# Relay.net
KiCad netlist of a schematic drawn in Altium Designer
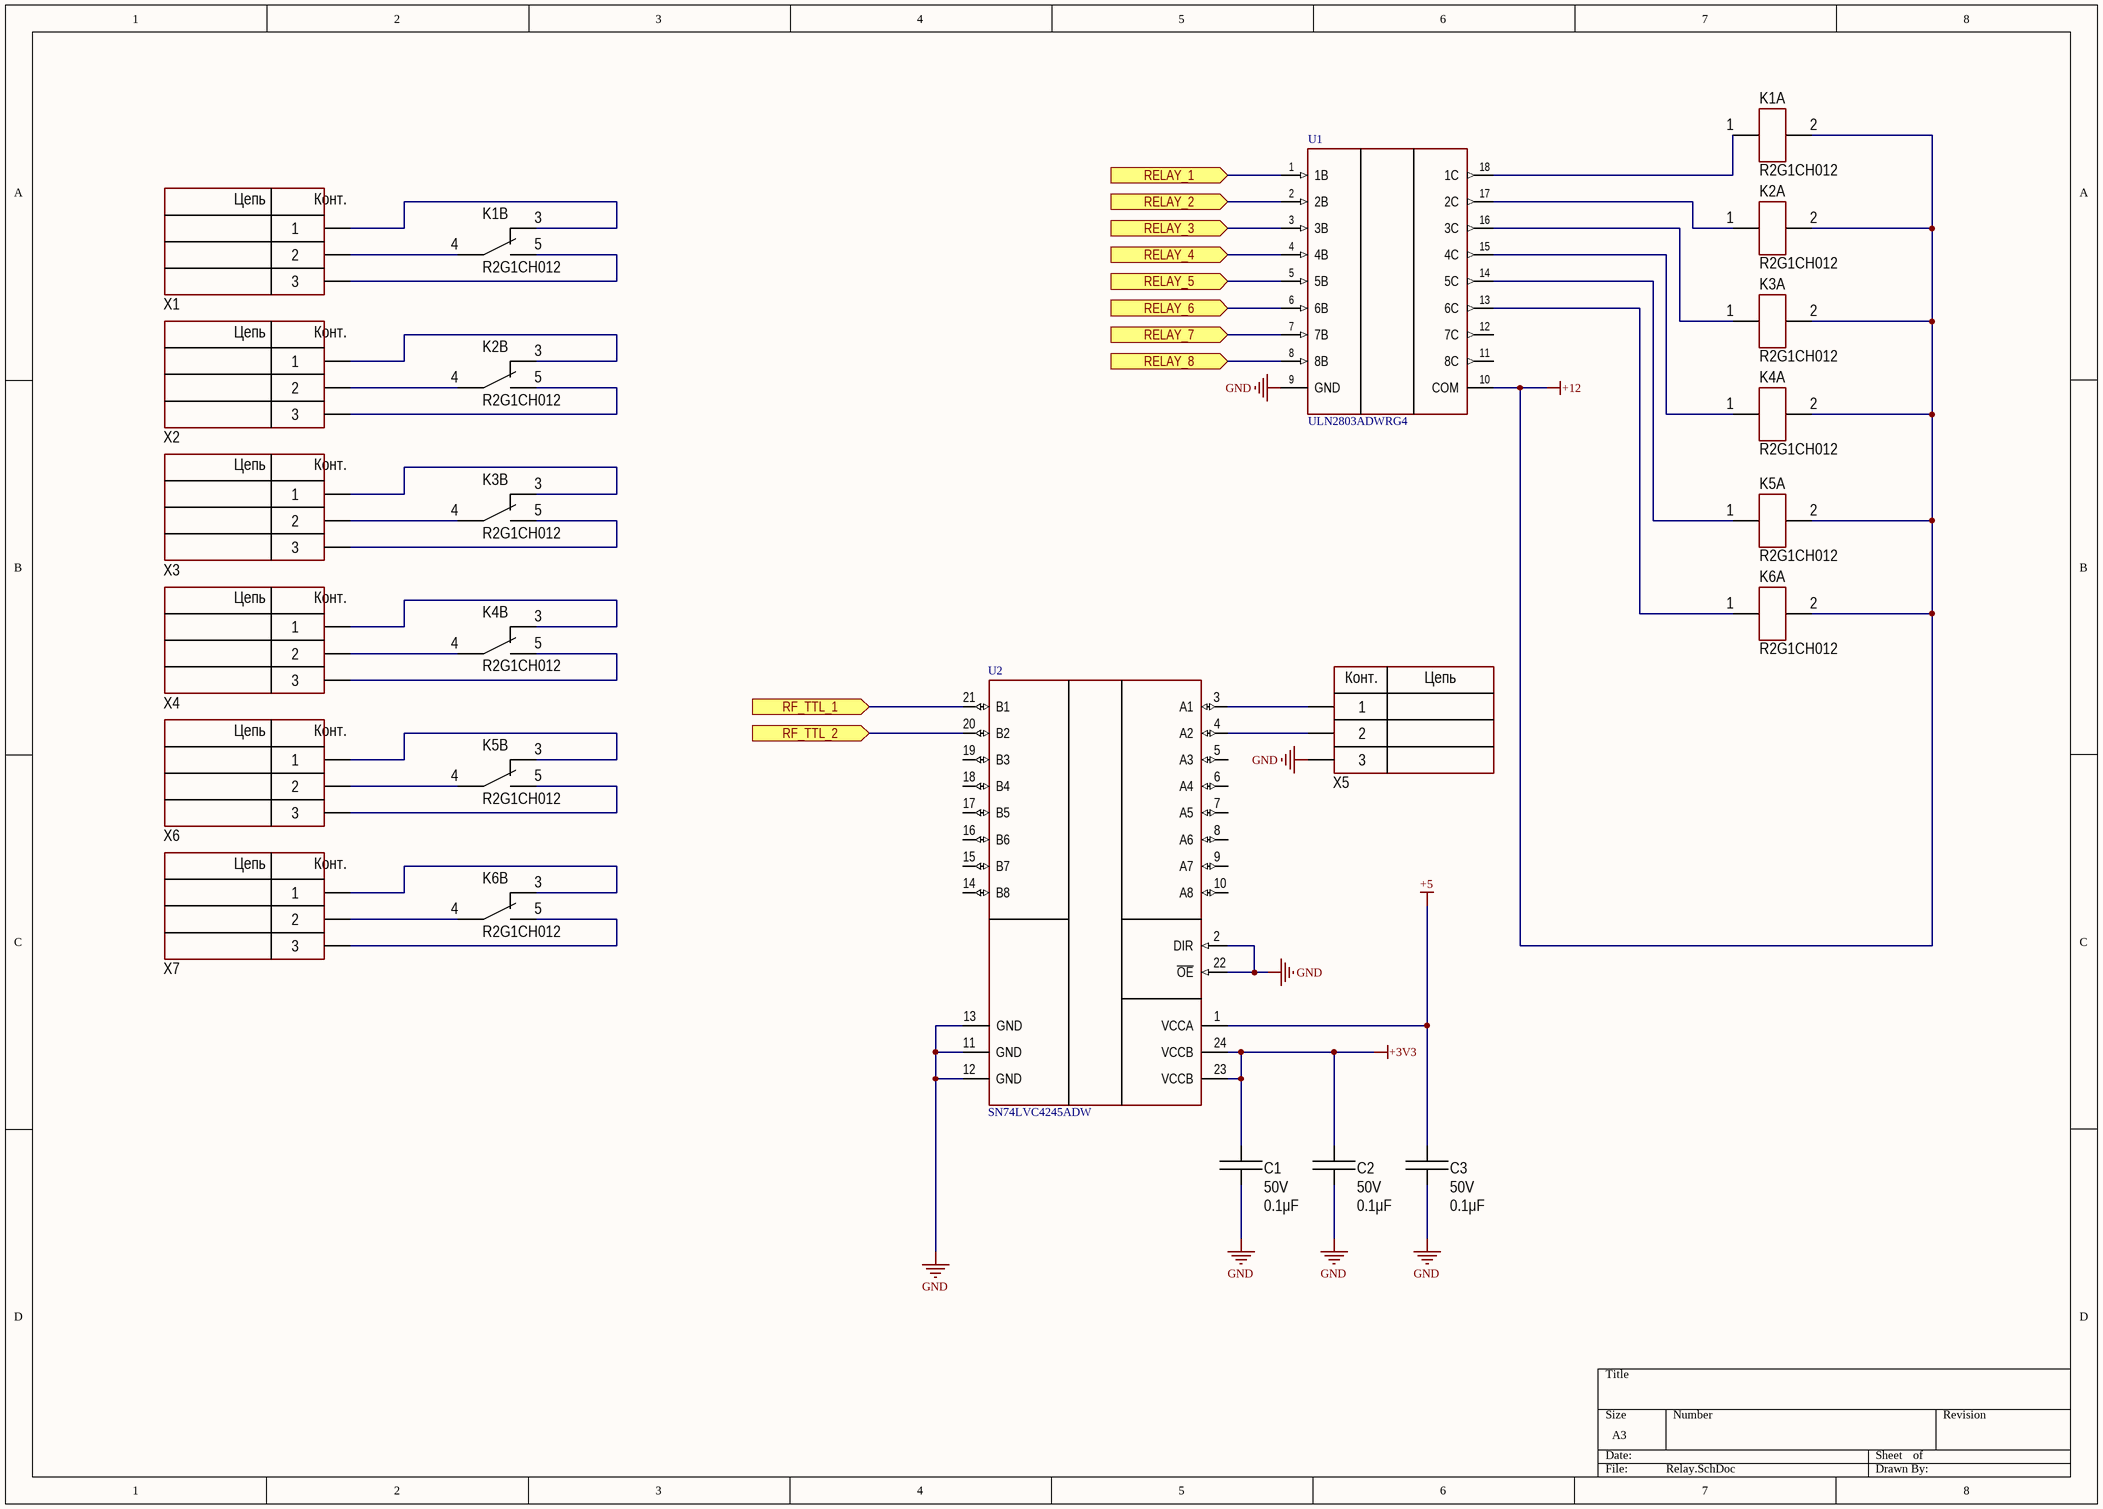
[diagram p0: Relay.SchDoc]

(export (version "E")
  (design (tool "Eeschema 10.0.6"))
  (components
    (comp (ref "C1")
      (value "0.1μF")
      (footprint "standard-case:CAP: 1206")
      (fields
        (field (name "MANUFACTURER") "Yageo")
        (field (name "PARTNUMBER") "CC1206KRX7R9BB104")
        (field (name "VALUEMANUFACTURERPARTNUMBER") "Ceramic capacitor, 0.1μF, X7R, ±10%, 50V, 1206, -55...+125°C")
        (field (name "VOLTAGE") "50V")
      )
      (libsource (lib "capacitor") (part "Ceramic_1206"))
    )
    (comp (ref "C2")
      (value "0.1μF")
      (footprint "standard-case:CAP: 1206")
      (fields
        (field (name "MANUFACTURER") "Yageo")
        (field (name "PARTNUMBER") "CC1206KRX7R9BB104")
        (field (name "VALUEMANUFACTURERPARTNUMBER") "Ceramic capacitor, 0.1μF, X7R, ±10%, 50V, 1206, -55...+125°C")
        (field (name "VOLTAGE") "50V")
      )
      (libsource (lib "capacitor") (part "Ceramic_1206"))
    )
    (comp (ref "C3")
      (value "0.1μF")
      (footprint "standard-case:CAP: 1206")
      (fields
        (field (name "MANUFACTURER") "Yageo")
        (field (name "PARTNUMBER") "CC1206KRX7R9BB104")
        (field (name "VALUEMANUFACTURERPARTNUMBER") "Ceramic capacitor, 0.1μF, X7R, ±10%, 50V, 1206, -55...+125°C")
        (field (name "VOLTAGE") "50V")
      )
      (libsource (lib "capacitor") (part "Ceramic_1206"))
    )
    (comp (ref "K1")
      (value "~")
      (footprint "R2G1CH012")
      (fields
        (field (name "MANUFACTURER") "Omron")
        (field (name "VALUEMANUFACTURERPARTNUMBER") "Electromechanics relay, 3VDC, 125VAC, 2A, 2NO+2NC, -40...+85°C")
        (field (name "PARTNUMBER") "R2G1CH012")
      )
      (libsource (lib "Реле R2G1CH012") (part "R2G1CH012"))
    )
    (comp (ref "K2")
      (value "~")
      (footprint "R2G1CH012")
      (fields
        (field (name "MANUFACTURER") "Omron")
        (field (name "VALUEMANUFACTURERPARTNUMBER") "Electromechanics relay, 3VDC, 125VAC, 2A, 2NO+2NC, -40...+85°C")
        (field (name "PARTNUMBER") "R2G1CH012")
      )
      (libsource (lib "Реле R2G1CH012") (part "R2G1CH012"))
    )
    (comp (ref "K3")
      (value "~")
      (footprint "R2G1CH012")
      (fields
        (field (name "MANUFACTURER") "Omron")
        (field (name "VALUEMANUFACTURERPARTNUMBER") "Electromechanics relay, 3VDC, 125VAC, 2A, 2NO+2NC, -40...+85°C")
        (field (name "PARTNUMBER") "R2G1CH012")
      )
      (libsource (lib "Реле R2G1CH012") (part "R2G1CH012"))
    )
    (comp (ref "K4")
      (value "~")
      (footprint "R2G1CH012")
      (fields
        (field (name "MANUFACTURER") "Omron")
        (field (name "VALUEMANUFACTURERPARTNUMBER") "Electromechanics relay, 3VDC, 125VAC, 2A, 2NO+2NC, -40...+85°C")
        (field (name "PARTNUMBER") "R2G1CH012")
      )
      (libsource (lib "Реле R2G1CH012") (part "R2G1CH012"))
    )
    (comp (ref "K5")
      (value "~")
      (footprint "R2G1CH012")
      (fields
        (field (name "MANUFACTURER") "Omron")
        (field (name "VALUEMANUFACTURERPARTNUMBER") "Electromechanics relay, 3VDC, 125VAC, 2A, 2NO+2NC, -40...+85°C")
        (field (name "PARTNUMBER") "R2G1CH012")
      )
      (libsource (lib "Реле R2G1CH012") (part "R2G1CH012"))
    )
    (comp (ref "K6")
      (value "~")
      (footprint "R2G1CH012")
      (fields
        (field (name "MANUFACTURER") "Omron")
        (field (name "VALUEMANUFACTURERPARTNUMBER") "Electromechanics relay, 3VDC, 125VAC, 2A, 2NO+2NC, -40...+85°C")
        (field (name "PARTNUMBER") "R2G1CH012")
      )
      (libsource (lib "Реле R2G1CH012") (part "R2G1CH012"))
    )
    (comp (ref "U1")
      (value "ULN2803ADWRG4")
      (footprint "FP-DW0018A-MFG")
      (description "TRANS 8NPN DARL 50V 0.5A 18SO")
      (fields
        (field (name "MANUFACTURER") "Texas Instruments")
        (field (name "OCTOPART") "https://octopart.com/uln2803adwrg4-texas+instruments-2343640")
      )
      (libsource (lib "ULN2803ADWR") (part "CMP-04912-000023-1"))
    )
    (comp (ref "U2")
      (value "SN74LVC4245ADW")
      (footprint "FP-DW0024A-MFG")
      (description "IC TRNSLTR BIDIRECTIONAL 24SOIC")
      (libsource (lib "SN74LVC4245ADW") (part "CMP-04899-000091-1"))
    )
    (comp (ref "X1")
      (value "~")
      (footprint "2EDGR-5.08-03P")
      (fields
        (field (name "MANUFACTURER") "Connfly")
        (field (name "VALUEMANUFACTURERPARTNUMBER") "Connector, 6pin, 2.54mm, 500VAC, 3A")
        (field (name "PARTNUMBER") "PBS-6")
      )
      (libsource (lib "") (part "2EDGR-5.08-03P_1"))
    )
    (comp (ref "X2")
      (value "~")
      (footprint "2EDGR-5.08-03P")
      (fields
        (field (name "MANUFACTURER") "Connfly")
        (field (name "VALUEMANUFACTURERPARTNUMBER") "Connector, 6pin, 2.54mm, 500VAC, 3A")
        (field (name "PARTNUMBER") "PBS-6")
      )
      (libsource (lib "") (part "2EDGR-5.08-03P_1"))
    )
    (comp (ref "X3")
      (value "~")
      (footprint "2EDGR-5.08-03P")
      (fields
        (field (name "MANUFACTURER") "Connfly")
        (field (name "VALUEMANUFACTURERPARTNUMBER") "Connector, 6pin, 2.54mm, 500VAC, 3A")
        (field (name "PARTNUMBER") "PBS-6")
      )
      (libsource (lib "") (part "2EDGR-5.08-03P_1"))
    )
    (comp (ref "X4")
      (value "~")
      (footprint "2EDGR-5.08-03P")
      (fields
        (field (name "MANUFACTURER") "Connfly")
        (field (name "VALUEMANUFACTURERPARTNUMBER") "Connector, 6pin, 2.54mm, 500VAC, 3A")
        (field (name "PARTNUMBER") "PBS-6")
      )
      (libsource (lib "") (part "2EDGR-5.08-03P_1"))
    )
    (comp (ref "X5")
      (value "~")
      (footprint "2EDGR-5.08-03P")
      (fields
        (field (name "MANUFACTURER") "Connfly")
        (field (name "VALUEMANUFACTURERPARTNUMBER") "Connector, 6pin, 2.54mm, 500VAC, 3A")
        (field (name "PARTNUMBER") "PBS-6")
      )
      (libsource (lib "K3NG_SCH_Libs") (part "2EDGR-5.08-03P"))
    )
    (comp (ref "X6")
      (value "~")
      (footprint "2EDGR-5.08-03P")
      (fields
        (field (name "MANUFACTURER") "Connfly")
        (field (name "VALUEMANUFACTURERPARTNUMBER") "Connector, 6pin, 2.54mm, 500VAC, 3A")
        (field (name "PARTNUMBER") "PBS-6")
      )
      (libsource (lib "") (part "2EDGR-5.08-03P_1"))
    )
    (comp (ref "X7")
      (value "~")
      (footprint "2EDGR-5.08-03P")
      (fields
        (field (name "MANUFACTURER") "Connfly")
        (field (name "VALUEMANUFACTURERPARTNUMBER") "Connector, 6pin, 2.54mm, 500VAC, 3A")
        (field (name "PARTNUMBER") "PBS-6")
      )
      (libsource (lib "") (part "2EDGR-5.08-03P_1"))
    )
  )
  (nets
    (net (code "1") (name "+3V3") (class "Default")
      (node (ref "C1") (pin "2") (pinfunction "2_2") (pintype "passive"))
      (node (ref "C2") (pin "2") (pinfunction "2_2") (pintype "passive"))
      (node (ref "U2") (pin "23") (pinfunction "VCCB_23") (pintype "power_in"))
      (node (ref "U2") (pin "24") (pinfunction "VCCB_24") (pintype "power_in"))
    )
    (net (code "2") (name "+5") (class "Default")
      (node (ref "C3") (pin "2") (pinfunction "2_2") (pintype "passive"))
      (node (ref "U2") (pin "1") (pinfunction "VCCA_1") (pintype "power_in"))
    )
    (net (code "3") (name "+12") (class "Default")
      (node (ref "K1") (pin "2") (pinfunction "2_2") (pintype "passive"))
      (node (ref "K2") (pin "2") (pinfunction "2_2") (pintype "passive"))
      (node (ref "K3") (pin "2") (pinfunction "2_2") (pintype "passive"))
      (node (ref "K4") (pin "2") (pinfunction "2_2") (pintype "passive"))
      (node (ref "K5") (pin "2") (pinfunction "2_2") (pintype "passive"))
      (node (ref "K6") (pin "2") (pinfunction "2_2") (pintype "passive"))
      (node (ref "U1") (pin "10") (pinfunction "COM_10") (pintype "power_in"))
    )
    (net (code "4") (name "/RELAY_1") (class "Default")
      (node (ref "U1") (pin "1") (pinfunction "1B_1") (pintype "input"))
    )
    (net (code "5") (name "/RELAY_2") (class "Default")
      (node (ref "U1") (pin "2") (pinfunction "2B_2") (pintype "input"))
    )
    (net (code "6") (name "/RELAY_3") (class "Default")
      (node (ref "U1") (pin "3") (pinfunction "3B_3") (pintype "input"))
    )
    (net (code "7") (name "/RELAY_4") (class "Default")
      (node (ref "U1") (pin "4") (pinfunction "4B_4") (pintype "input"))
    )
    (net (code "8") (name "/RELAY_5") (class "Default")
      (node (ref "U1") (pin "5") (pinfunction "5B_5") (pintype "input"))
    )
    (net (code "9") (name "/RELAY_6") (class "Default")
      (node (ref "U1") (pin "6") (pinfunction "6B_6") (pintype "input"))
    )
    (net (code "10") (name "/RELAY_7") (class "Default")
      (node (ref "U1") (pin "7") (pinfunction "7B_7") (pintype "input"))
    )
    (net (code "11") (name "/RELAY_8") (class "Default")
      (node (ref "U1") (pin "8") (pinfunction "8B_8") (pintype "input"))
    )
    (net (code "12") (name "/RF_TTL_1") (class "Default")
      (node (ref "U2") (pin "21") (pinfunction "B1_21") (pintype "bidirectional"))
    )
    (net (code "13") (name "/RF_TTL_2") (class "Default")
      (node (ref "U2") (pin "20") (pinfunction "B2_20") (pintype "bidirectional"))
    )
    (net (code "14") (name "GND") (class "Default")
      (node (ref "C1") (pin "1") (pinfunction "1_1") (pintype "passive"))
      (node (ref "C2") (pin "1") (pinfunction "1_1") (pintype "passive"))
      (node (ref "C3") (pin "1") (pinfunction "1_1") (pintype "passive"))
      (node (ref "U1") (pin "9") (pinfunction "GND_9") (pintype "power_in"))
      (node (ref "U2") (pin "11") (pinfunction "GND_11") (pintype "power_in"))
      (node (ref "U2") (pin "12") (pinfunction "GND_12") (pintype "power_in"))
      (node (ref "U2") (pin "2") (pinfunction "DIR_2") (pintype "input"))
      (node (ref "U2") (pin "22") (pinfunction "~{OE}_22") (pintype "input"))
      (node (ref "X5") (pin "3") (pinfunction "3_3") (pintype "power_in"))
    )
    (net (code "15") (name "Net-(K1-Pad3)") (class "Default")
      (node (ref "K1") (pin "3") (pinfunction "3_3") (pintype "passive"))
      (node (ref "X1") (pin "1") (pinfunction "1_1") (pintype "passive"))
    )
    (net (code "16") (name "Net-(K1-Pad4)") (class "Default")
      (node (ref "K1") (pin "4") (pinfunction "4_4") (pintype "passive"))
      (node (ref "X1") (pin "2") (pinfunction "2_2") (pintype "passive"))
    )
    (net (code "17") (name "Net-(K1-Pad5)") (class "Default")
      (node (ref "K1") (pin "5") (pinfunction "5_5") (pintype "passive"))
      (node (ref "X1") (pin "3") (pinfunction "3_3") (pintype "power_in"))
    )
    (net (code "18") (name "Net-(K2-Pad3)") (class "Default")
      (node (ref "K2") (pin "3") (pinfunction "3_3") (pintype "passive"))
      (node (ref "X2") (pin "1") (pinfunction "1_1") (pintype "passive"))
    )
    (net (code "19") (name "Net-(K2-Pad4)") (class "Default")
      (node (ref "K2") (pin "4") (pinfunction "4_4") (pintype "passive"))
      (node (ref "X2") (pin "2") (pinfunction "2_2") (pintype "passive"))
    )
    (net (code "20") (name "Net-(K2-Pad5)") (class "Default")
      (node (ref "K2") (pin "5") (pinfunction "5_5") (pintype "passive"))
      (node (ref "X2") (pin "3") (pinfunction "3_3") (pintype "power_in"))
    )
    (net (code "21") (name "Net-(K3-Pad3)") (class "Default")
      (node (ref "K3") (pin "3") (pinfunction "3_3") (pintype "passive"))
      (node (ref "X3") (pin "1") (pinfunction "1_1") (pintype "passive"))
    )
    (net (code "22") (name "Net-(K3-Pad4)") (class "Default")
      (node (ref "K3") (pin "4") (pinfunction "4_4") (pintype "passive"))
      (node (ref "X3") (pin "2") (pinfunction "2_2") (pintype "passive"))
    )
    (net (code "23") (name "Net-(K3-Pad5)") (class "Default")
      (node (ref "K3") (pin "5") (pinfunction "5_5") (pintype "passive"))
      (node (ref "X3") (pin "3") (pinfunction "3_3") (pintype "power_in"))
    )
    (net (code "24") (name "Net-(K4-Pad3)") (class "Default")
      (node (ref "K4") (pin "3") (pinfunction "3_3") (pintype "passive"))
      (node (ref "X4") (pin "1") (pinfunction "1_1") (pintype "passive"))
    )
    (net (code "25") (name "Net-(K4-Pad4)") (class "Default")
      (node (ref "K4") (pin "4") (pinfunction "4_4") (pintype "passive"))
      (node (ref "X4") (pin "2") (pinfunction "2_2") (pintype "passive"))
    )
    (net (code "26") (name "Net-(K4-Pad5)") (class "Default")
      (node (ref "K4") (pin "5") (pinfunction "5_5") (pintype "passive"))
      (node (ref "X4") (pin "3") (pinfunction "3_3") (pintype "power_in"))
    )
    (net (code "27") (name "Net-(K5-Pad3)") (class "Default")
      (node (ref "K5") (pin "3") (pinfunction "3_3") (pintype "passive"))
      (node (ref "X6") (pin "1") (pinfunction "1_1") (pintype "passive"))
    )
    (net (code "28") (name "Net-(K5-Pad4)") (class "Default")
      (node (ref "K5") (pin "4") (pinfunction "4_4") (pintype "passive"))
      (node (ref "X6") (pin "2") (pinfunction "2_2") (pintype "passive"))
    )
    (net (code "29") (name "Net-(K5-Pad5)") (class "Default")
      (node (ref "K5") (pin "5") (pinfunction "5_5") (pintype "passive"))
      (node (ref "X6") (pin "3") (pinfunction "3_3") (pintype "power_in"))
    )
    (net (code "30") (name "Net-(K6-Pad3)") (class "Default")
      (node (ref "K6") (pin "3") (pinfunction "3_3") (pintype "passive"))
      (node (ref "X7") (pin "1") (pinfunction "1_1") (pintype "passive"))
    )
    (net (code "31") (name "Net-(K6-Pad4)") (class "Default")
      (node (ref "K6") (pin "4") (pinfunction "4_4") (pintype "passive"))
      (node (ref "X7") (pin "2") (pinfunction "2_2") (pintype "passive"))
    )
    (net (code "32") (name "Net-(K6-Pad5)") (class "Default")
      (node (ref "K6") (pin "5") (pinfunction "5_5") (pintype "passive"))
      (node (ref "X7") (pin "3") (pinfunction "3_3") (pintype "power_in"))
    )
    (net (code "33") (name "Net-(U1-1C)") (class "Default")
      (node (ref "K1") (pin "1") (pinfunction "1_1") (pintype "passive"))
      (node (ref "U1") (pin "18") (pinfunction "1C_18") (pintype "output"))
    )
    (net (code "34") (name "Net-(U1-2C)") (class "Default")
      (node (ref "K2") (pin "1") (pinfunction "1_1") (pintype "passive"))
      (node (ref "U1") (pin "17") (pinfunction "2C_17") (pintype "output"))
    )
    (net (code "35") (name "Net-(U1-3C)") (class "Default")
      (node (ref "K3") (pin "1") (pinfunction "1_1") (pintype "passive"))
      (node (ref "U1") (pin "16") (pinfunction "3C_16") (pintype "output"))
    )
    (net (code "36") (name "Net-(U1-4C)") (class "Default")
      (node (ref "K4") (pin "1") (pinfunction "1_1") (pintype "passive"))
      (node (ref "U1") (pin "15") (pinfunction "4C_15") (pintype "output"))
    )
    (net (code "37") (name "Net-(U1-5C)") (class "Default")
      (node (ref "K5") (pin "1") (pinfunction "1_1") (pintype "passive"))
      (node (ref "U1") (pin "14") (pinfunction "5C_14") (pintype "output"))
    )
    (net (code "38") (name "Net-(U1-6C)") (class "Default")
      (node (ref "K6") (pin "1") (pinfunction "1_1") (pintype "passive"))
      (node (ref "U1") (pin "13") (pinfunction "6C_13") (pintype "output"))
    )
    (net (code "39") (name "Net-(U2-A1)") (class "Default")
      (node (ref "U2") (pin "3") (pinfunction "A1_3") (pintype "bidirectional"))
      (node (ref "X5") (pin "1") (pinfunction "1_1") (pintype "passive"))
    )
    (net (code "40") (name "Net-(U2-A2)") (class "Default")
      (node (ref "U2") (pin "4") (pinfunction "A2_4") (pintype "bidirectional"))
      (node (ref "X5") (pin "2") (pinfunction "2_2") (pintype "passive"))
    )
    (net (code "41") (name "unconnected-(U1-7C-Pad12)") (class "Default")
      (node (ref "U1") (pin "12") (pinfunction "7C_12") (pintype "output"))
    )
    (net (code "42") (name "unconnected-(U1-8C-Pad11)") (class "Default")
      (node (ref "U1") (pin "11") (pinfunction "8C_11") (pintype "output"))
    )
    (net (code "43") (name "unconnected-(U2-A3-Pad5)") (class "Default")
      (node (ref "U2") (pin "5") (pinfunction "A3_5") (pintype "bidirectional"))
    )
    (net (code "44") (name "unconnected-(U2-A4-Pad6)") (class "Default")
      (node (ref "U2") (pin "6") (pinfunction "A4_6") (pintype "bidirectional"))
    )
    (net (code "45") (name "unconnected-(U2-A5-Pad7)") (class "Default")
      (node (ref "U2") (pin "7") (pinfunction "A5_7") (pintype "bidirectional"))
    )
    (net (code "46") (name "unconnected-(U2-A6-Pad8)") (class "Default")
      (node (ref "U2") (pin "8") (pinfunction "A6_8") (pintype "bidirectional"))
    )
    (net (code "47") (name "unconnected-(U2-A7-Pad9)") (class "Default")
      (node (ref "U2") (pin "9") (pinfunction "A7_9") (pintype "bidirectional"))
    )
    (net (code "48") (name "unconnected-(U2-A8-Pad10)") (class "Default")
      (node (ref "U2") (pin "10") (pinfunction "A8_10") (pintype "bidirectional"))
    )
    (net (code "49") (name "unconnected-(U2-B3-Pad19)") (class "Default")
      (node (ref "U2") (pin "19") (pinfunction "B3_19") (pintype "bidirectional"))
    )
    (net (code "50") (name "unconnected-(U2-B4-Pad18)") (class "Default")
      (node (ref "U2") (pin "18") (pinfunction "B4_18") (pintype "bidirectional"))
    )
    (net (code "51") (name "unconnected-(U2-B5-Pad17)") (class "Default")
      (node (ref "U2") (pin "17") (pinfunction "B5_17") (pintype "bidirectional"))
    )
    (net (code "52") (name "unconnected-(U2-B6-Pad16)") (class "Default")
      (node (ref "U2") (pin "16") (pinfunction "B6_16") (pintype "bidirectional"))
    )
    (net (code "53") (name "unconnected-(U2-B7-Pad15)") (class "Default")
      (node (ref "U2") (pin "15") (pinfunction "B7_15") (pintype "bidirectional"))
    )
    (net (code "54") (name "unconnected-(U2-B8-Pad14)") (class "Default")
      (node (ref "U2") (pin "14") (pinfunction "B8_14") (pintype "bidirectional"))
    )
    (net (code "55") (name "unconnected-(U2-GND-Pad13)") (class "Default")
      (node (ref "U2") (pin "13") (pinfunction "GND_13") (pintype "power_in"))
    )
  )
)
